# HB-power_v1_2.net
KiCad netlist of a schematic drawn in EAGLE
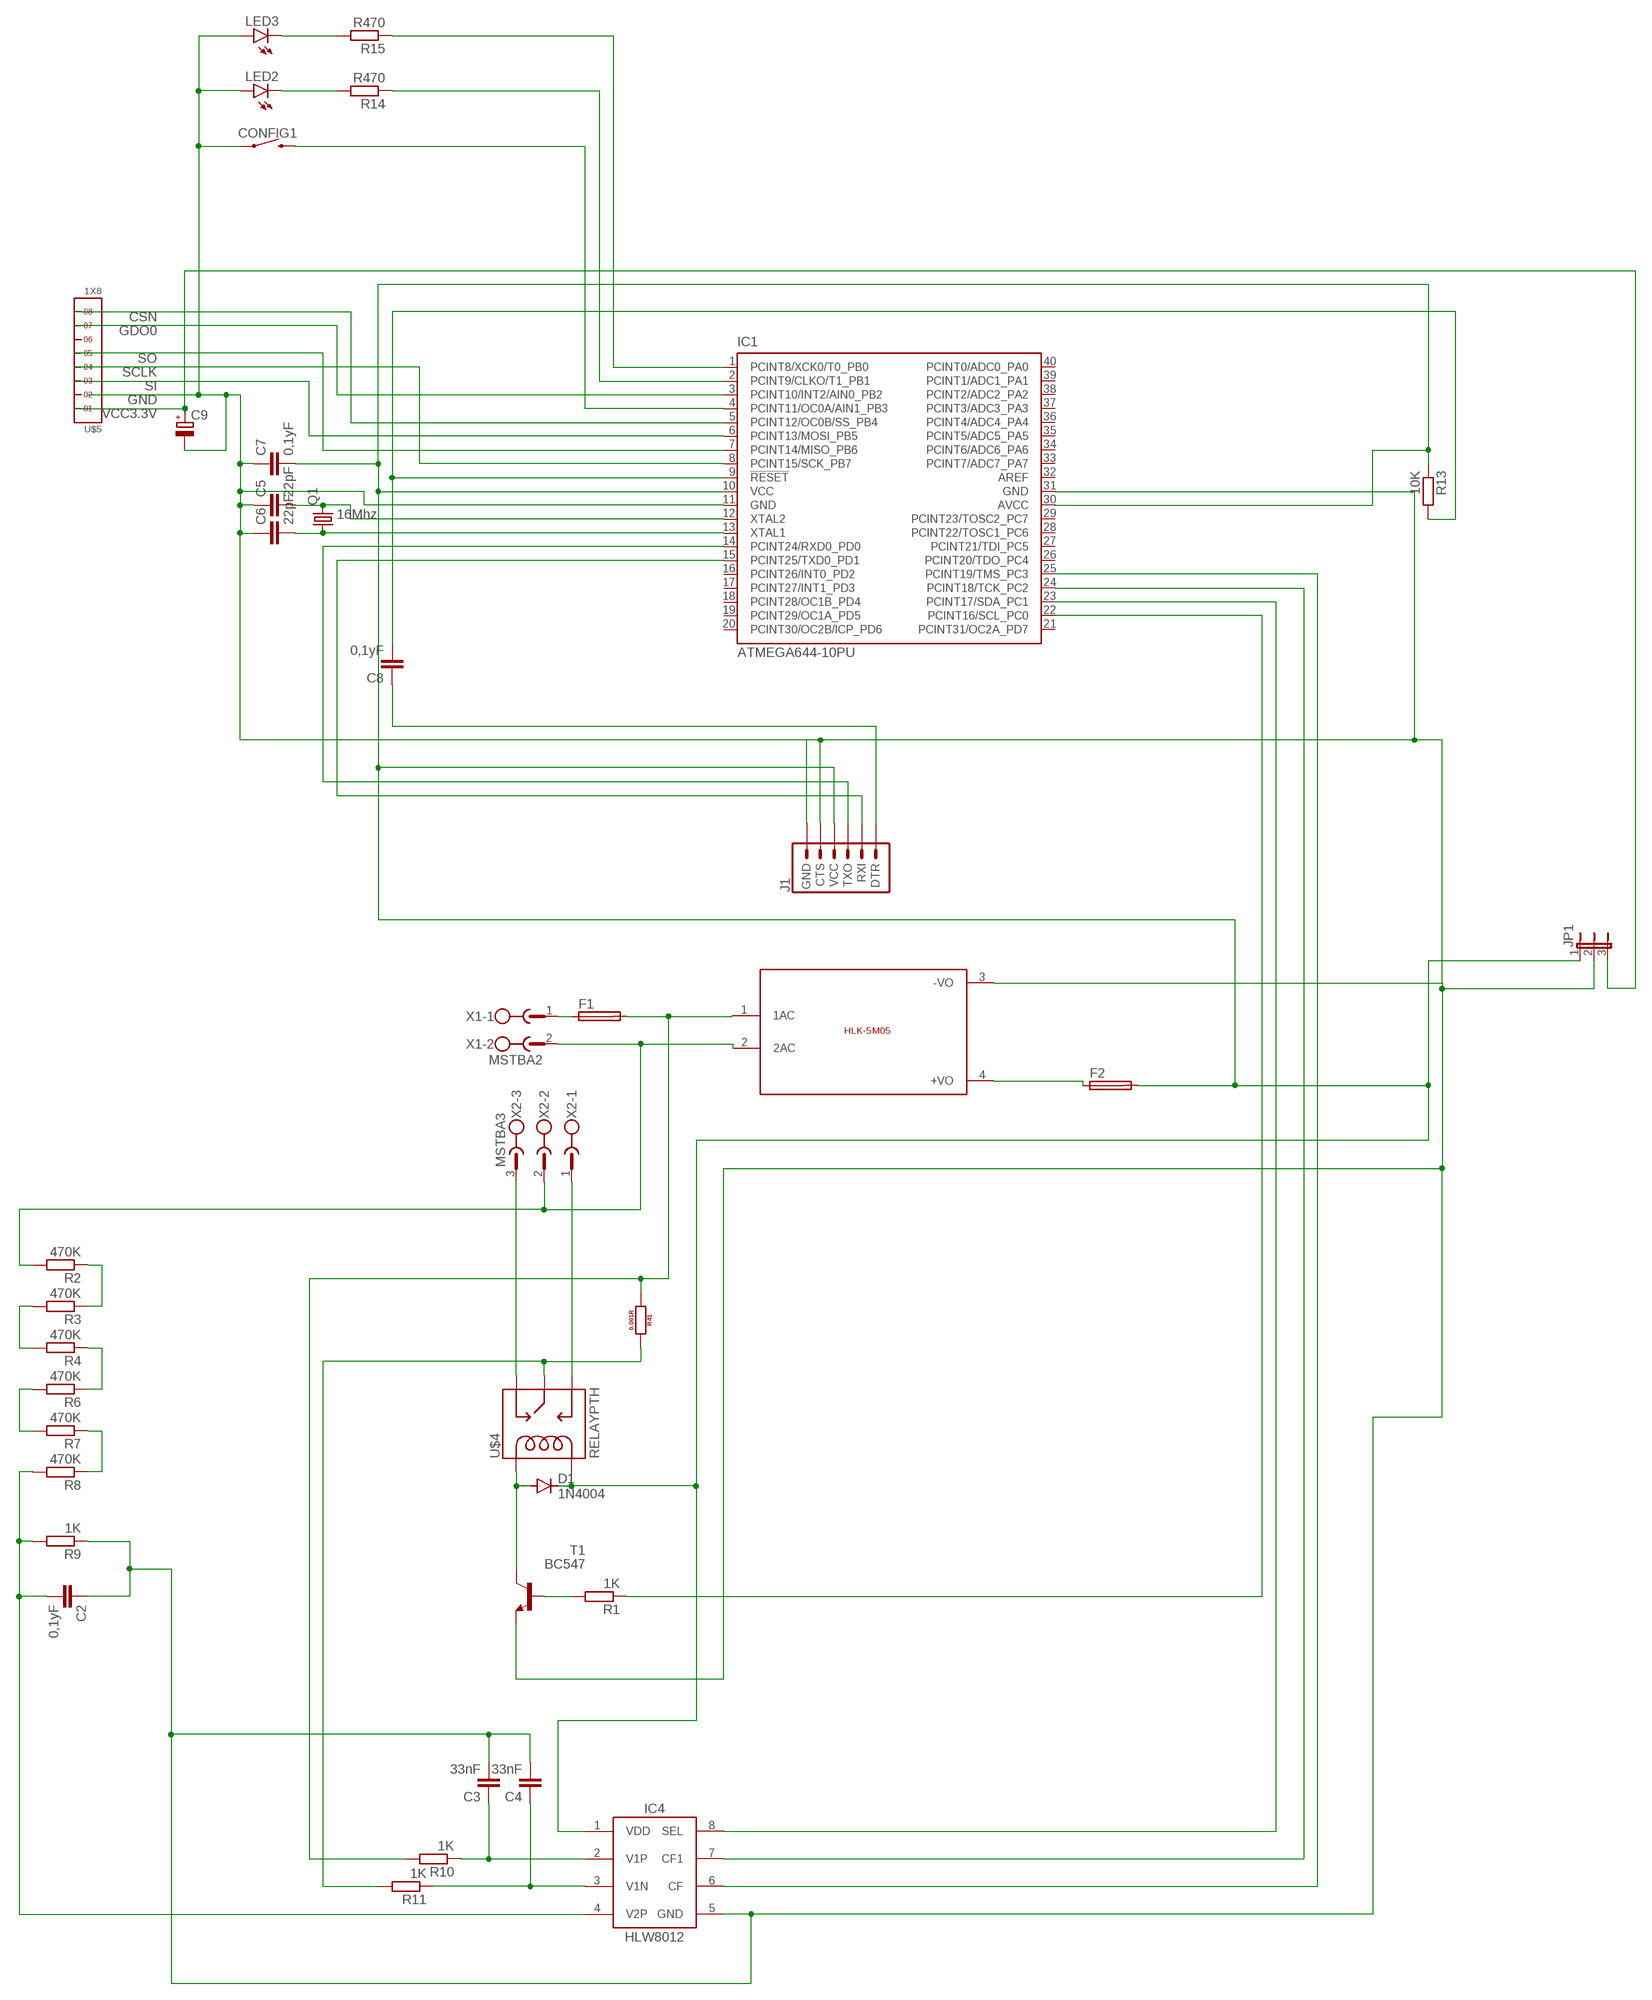
[diagram p0: schematic, sheet 1]

(export (version "E")
  (design (tool "Eeschema 10.0.6"))
  (components
    (comp (ref "C2")
      (value "0,1yF")
      (footprint "eagle-import:C050-024X044")
      (libsource (lib "eagle-import") (part "C-EU050-024X044"))
    )
    (comp (ref "C3")
      (value "33nF")
      (footprint "eagle-import:C050-024X044")
      (libsource (lib "eagle-import") (part "C-EU050-024X044"))
    )
    (comp (ref "C4")
      (value "33nF")
      (footprint "eagle-import:C050-024X044")
      (libsource (lib "eagle-import") (part "C-EU050-024X044"))
    )
    (comp (ref "C5")
      (value "22pF")
      (footprint "eagle-import:C025-024X044")
      (libsource (lib "eagle-import") (part "C-EU025-024X044"))
    )
    (comp (ref "C6")
      (value "22pF")
      (footprint "eagle-import:C025-024X044")
      (libsource (lib "eagle-import") (part "C-EU025-024X044"))
    )
    (comp (ref "C7")
      (value "0,1yF")
      (footprint "eagle-import:C025-024X044")
      (libsource (lib "eagle-import") (part "C-EU025-024X044"))
    )
    (comp (ref "C8")
      (value "0,1yF")
      (footprint "eagle-import:C025-024X044")
      (libsource (lib "eagle-import") (part "C-EU025-024X044"))
    )
    (comp (ref "C9")
      (value "CPOL-EUE2.5-5")
      (footprint "eagle-import:E2,5-5")
      (libsource (lib "eagle-import") (part "CPOL-EUE2.5-5"))
    )
    (comp (ref "CONFIG1")
      (value "MOMENTARY-SWITCH-SPST-PTH-6.0MM-KIT")
      (footprint "eagle-import:TACTILE_SWITCH_PTH_6.0MM_KIT")
      (libsource (lib "eagle-import") (part "MOMENTARY-SWITCH-SPST-PTH-6.0MM-KIT"))
    )
    (comp (ref "D1")
      (value "1N4004")
      (footprint "eagle-import:DO41-10")
      (libsource (lib "eagle-import") (part "1N4004"))
    )
    (comp (ref "F1")
      (value "SH22,5A")
      (footprint "eagle-import:SH22,5A")
      (fields (field (name "MPN") "0031.7701.11"))
      (libsource (lib "eagle-import") (part "SH22,5A"))
    )
    (comp (ref "F2")
      (value "SH22,5A")
      (footprint "eagle-import:SH22,5A")
      (fields (field (name "MPN") "0031.7701.11"))
      (libsource (lib "eagle-import") (part "SH22,5A"))
    )
    (comp (ref "IC1")
      (value "ATMEGA644-10PU")
      (footprint "eagle-import:DIL40")
      (fields (field (name "MPN") "ATMEGA644V-10PU"))
      (libsource (lib "eagle-import") (part "ATMEGA644-PU10"))
    )
    (comp (ref "IC4")
      (value "HLW8012")
      (footprint "eagle-import:SOP8")
      (libsource (lib "eagle-import") (part "HLW8012"))
    )
    (comp (ref "J1")
      (value "6_PIN_SERIAL_TARGETLONGPADS")
      (footprint "eagle-import:1X06_LONGPADS")
      (libsource (lib "eagle-import") (part "6_PIN_SERIAL_TARGETLONGPADS"))
    )
    (comp (ref "JP1")
      (value "JP2E")
      (footprint "eagle-import:JP2")
      (libsource (lib "eagle-import") (part "JP2E"))
    )
    (comp (ref "LED2")
      (value "LED3MM")
      (footprint "eagle-import:LED3MM")
      (libsource (lib "eagle-import") (part "LED3MM"))
    )
    (comp (ref "LED3")
      (value "LED3MM")
      (footprint "eagle-import:LED3MM")
      (libsource (lib "eagle-import") (part "LED3MM"))
    )
    (comp (ref "Q1")
      (value "16Mhz")
      (footprint "eagle-import:HC49U-V")
      (libsource (lib "eagle-import") (part "CRYSTALHC49U-V"))
    )
    (comp (ref "R1")
      (value "1K")
      (footprint "eagle-import:0309_10")
      (libsource (lib "eagle-import") (part "R-EU_0309/10"))
    )
    (comp (ref "R2")
      (value "470K")
      (footprint "eagle-import:0309_10")
      (libsource (lib "eagle-import") (part "R-EU_0309/10"))
    )
    (comp (ref "R3")
      (value "470K")
      (footprint "eagle-import:0309_10")
      (libsource (lib "eagle-import") (part "R-EU_0309/10"))
    )
    (comp (ref "R4")
      (value "470K")
      (footprint "eagle-import:0309_10")
      (libsource (lib "eagle-import") (part "R-EU_0309/10"))
    )
    (comp (ref "R6")
      (value "470K")
      (footprint "eagle-import:0309_10")
      (libsource (lib "eagle-import") (part "R-EU_0309/10"))
    )
    (comp (ref "R7")
      (value "470K")
      (footprint "eagle-import:0309_10")
      (libsource (lib "eagle-import") (part "R-EU_0309/10"))
    )
    (comp (ref "R8")
      (value "470K")
      (footprint "eagle-import:0309_10")
      (libsource (lib "eagle-import") (part "R-EU_0309/10"))
    )
    (comp (ref "R9")
      (value "1K")
      (footprint "eagle-import:0309_10")
      (libsource (lib "eagle-import") (part "R-EU_0309/10"))
    )
    (comp (ref "R10")
      (value "1K")
      (footprint "eagle-import:0309_10")
      (libsource (lib "eagle-import") (part "R-EU_0309/10"))
    )
    (comp (ref "R11")
      (value "1K")
      (footprint "eagle-import:0309_10")
      (libsource (lib "eagle-import") (part "R-EU_0309/10"))
    )
    (comp (ref "R13")
      (value "10K")
      (footprint "eagle-import:0309_10")
      (libsource (lib "eagle-import") (part "R-EU_0309/10"))
    )
    (comp (ref "R14")
      (value "R470")
      (footprint "eagle-import:0309_10")
      (libsource (lib "eagle-import") (part "R-EU_0309/10"))
    )
    (comp (ref "R15")
      (value "R470")
      (footprint "eagle-import:0309_10")
      (libsource (lib "eagle-import") (part "R-EU_0309/10"))
    )
    (comp (ref "R41")
      (value "0.001R")
      (footprint "eagle-import:2512")
      (libsource (lib "eagle-import") (part "RESISTOR2512"))
    )
    (comp (ref "T1")
      (value "BC547")
      (footprint "eagle-import:TO92")
      (libsource (lib "eagle-import") (part "BC547"))
    )
    (comp (ref "U$3")
      (value "5VDC/5W")
      (footprint "eagle-import:HLK-5M05")
      (libsource (lib "eagle-import") (part "HLK-5M05"))
    )
    (comp (ref "U$4")
      (value "RELAYPTH")
      (footprint "eagle-import:SRD-05VDC-SL-C")
      (libsource (lib "eagle-import") (part "RELAYPTH"))
    )
    (comp (ref "U$5")
      (value "1X8")
      (footprint "eagle-import:1X8")
      (libsource (lib "eagle-import") (part "1X8"))
    )
    (comp (ref "X1")
      (value "MSTBA2")
      (footprint "eagle-import:MSTBA2")
      (fields (field (name "MF") "FARNELL") (field (name "MPN") "1757242"))
      (libsource (lib "eagle-import") (part "MSTBA2"))
    )
    (comp (ref "X2")
      (value "MSTBA3")
      (footprint "eagle-import:MSTBA3")
      (fields (field (name "MF") "FARNELL") (field (name "MPN") "1757255"))
      (libsource (lib "eagle-import") (part "MSTBA3"))
    )
  )
  (nets
    (net (code "1") (name "/CSN") (class "Default")
      (node (ref "IC1") (pin "5") (pinfunction "PCINT12/OC0B/SS_PB4_5") (pintype "bidirectional"))
      (node (ref "U$5") (pin "8") (pinfunction "8_8") (pintype "bidirectional"))
    )
    (net (code "2") (name "/GDO0") (class "Default")
      (node (ref "IC1") (pin "3") (pinfunction "PCINT10/INT2/AIN0_PB2_3") (pintype "bidirectional"))
      (node (ref "U$5") (pin "7") (pinfunction "7_7") (pintype "bidirectional"))
    )
    (net (code "3") (name "/GND") (class "Default")
      (node (ref "C2") (pin "1") (pinfunction "1_1") (pintype "passive"))
      (node (ref "C3") (pin "2") (pinfunction "2_2") (pintype "passive"))
      (node (ref "C4") (pin "2") (pinfunction "2_2") (pintype "passive"))
      (node (ref "C5") (pin "1") (pinfunction "1_1") (pintype "passive"))
      (node (ref "C6") (pin "1") (pinfunction "1_1") (pintype "passive"))
      (node (ref "C7") (pin "1") (pinfunction "1_1") (pintype "passive"))
      (node (ref "C9") (pin "-") (pinfunction "-_-") (pintype "passive"))
      (node (ref "CONFIG1") (pin "1") (pinfunction "1_1") (pintype "passive"))
      (node (ref "IC1") (pin "11") (pinfunction "GND_11") (pintype "power_in"))
      (node (ref "IC1") (pin "31") (pinfunction "GND_31") (pintype "power_in"))
      (node (ref "IC4") (pin "5") (pinfunction "GND_5") (pintype "power_in"))
      (node (ref "J1") (pin "5") (pinfunction "CTS_5") (pintype "passive"))
      (node (ref "J1") (pin "6") (pinfunction "GND_6") (pintype "passive"))
      (node (ref "JP1") (pin "2") (pinfunction "2_2") (pintype "passive"))
      (node (ref "LED2") (pin "A") (pinfunction "A_A") (pintype "passive"))
      (node (ref "LED3") (pin "A") (pinfunction "A_A") (pintype "passive"))
      (node (ref "R9") (pin "1") (pinfunction "1_1") (pintype "passive"))
      (node (ref "T1") (pin "1") (pinfunction "E_1") (pintype "passive"))
      (node (ref "U$3") (pin "3") (pinfunction "-VO_3") (pintype "bidirectional"))
    )
    (net (code "4") (name "/SCLK") (class "Default")
      (node (ref "IC1") (pin "8") (pinfunction "PCINT15/SCK_PB7_8") (pintype "bidirectional"))
      (node (ref "U$5") (pin "4") (pinfunction "4_4") (pintype "bidirectional"))
    )
    (net (code "5") (name "/SI") (class "Default")
      (node (ref "IC1") (pin "6") (pinfunction "PCINT13/MOSI_PB5_6") (pintype "bidirectional"))
      (node (ref "U$5") (pin "3") (pinfunction "3_3") (pintype "bidirectional"))
    )
    (net (code "6") (name "/SO") (class "Default")
      (node (ref "IC1") (pin "7") (pinfunction "PCINT14/MISO_PB6_7") (pintype "bidirectional"))
      (node (ref "U$5") (pin "5") (pinfunction "5_5") (pintype "bidirectional"))
    )
    (net (code "7") (name "/VCC3.3V") (class "Default")
      (node (ref "C9") (pin "+") (pinfunction "+_+") (pintype "passive"))
      (node (ref "JP1") (pin "3") (pinfunction "3_3") (pintype "passive"))
      (node (ref "U$5") (pin "1") (pinfunction "1_1") (pintype "bidirectional"))
    )
    (net (code "8") (name "Net-(CONFIG1-2)") (class "Default")
      (node (ref "CONFIG1") (pin "3") (pinfunction "2_3") (pintype "passive"))
      (node (ref "IC1") (pin "4") (pinfunction "PCINT11/OC0A/AIN1_PB3_4") (pintype "bidirectional"))
    )
    (net (code "9") (name "Net-(F1-Pad1)") (class "Default")
      (node (ref "F1") (pin "1") (pinfunction "1_1") (pintype "passive"))
      (node (ref "X1") (pin "1") (pinfunction "1_1") (pintype "passive"))
    )
    (net (code "10") (name "Net-(IC1-AVCC)") (class "Default")
      (node (ref "C7") (pin "2") (pinfunction "2_2") (pintype "passive"))
      (node (ref "D1") (pin "C") (pinfunction "C_C") (pintype "passive"))
      (node (ref "F2") (pin "2") (pinfunction "2_2") (pintype "passive"))
      (node (ref "IC1") (pin "10") (pinfunction "VCC_10") (pintype "power_in"))
      (node (ref "IC1") (pin "30") (pinfunction "AVCC_30") (pintype "power_in"))
      (node (ref "IC4") (pin "1") (pinfunction "VDD_1") (pintype "power_in"))
      (node (ref "J1") (pin "4") (pinfunction "VCC_4") (pintype "passive"))
      (node (ref "JP1") (pin "1") (pinfunction "1_1") (pintype "passive"))
      (node (ref "R13") (pin "1") (pinfunction "1_1") (pintype "passive"))
      (node (ref "U$4") (pin "COIL0") (pinfunction "COIL0_COIL0") (pintype "bidirectional"))
    )
    (net (code "11") (name "Net-(IC1-PCINT8{slash}XCK0{slash}T0_PB0)") (class "Default")
      (node (ref "IC1") (pin "1") (pinfunction "PCINT8/XCK0/T0_PB0_1") (pintype "bidirectional"))
      (node (ref "R15") (pin "1") (pinfunction "1_1") (pintype "passive"))
    )
    (net (code "12") (name "Net-(IC1-PCINT9{slash}CLKO{slash}T1_PB1)") (class "Default")
      (node (ref "IC1") (pin "2") (pinfunction "PCINT9/CLKO/T1_PB1_2") (pintype "bidirectional"))
      (node (ref "R14") (pin "1") (pinfunction "1_1") (pintype "passive"))
    )
    (net (code "13") (name "Net-(IC1-PCINT16{slash}SCL_PC0)") (class "Default")
      (node (ref "IC1") (pin "22") (pinfunction "PCINT16/SCL_PC0_22") (pintype "bidirectional"))
      (node (ref "R1") (pin "1") (pinfunction "1_1") (pintype "passive"))
    )
    (net (code "14") (name "Net-(IC1-PCINT17{slash}SDA_PC1)") (class "Default")
      (node (ref "IC1") (pin "23") (pinfunction "PCINT17/SDA_PC1_23") (pintype "bidirectional"))
      (node (ref "IC4") (pin "8") (pinfunction "SEL_8") (pintype "input"))
    )
    (net (code "15") (name "Net-(IC1-PCINT18{slash}TCK_PC2)") (class "Default")
      (node (ref "IC1") (pin "24") (pinfunction "PCINT18/TCK_PC2_24") (pintype "bidirectional"))
      (node (ref "IC4") (pin "7") (pinfunction "CF1_7") (pintype "output"))
    )
    (net (code "16") (name "Net-(IC1-PCINT19{slash}TMS_PC3)") (class "Default")
      (node (ref "IC1") (pin "25") (pinfunction "PCINT19/TMS_PC3_25") (pintype "bidirectional"))
      (node (ref "IC4") (pin "6") (pinfunction "CF_6") (pintype "output"))
    )
    (net (code "17") (name "Net-(IC1-PCINT24{slash}RXD0_PD0)") (class "Default")
      (node (ref "IC1") (pin "14") (pinfunction "PCINT24/RXD0_PD0_14") (pintype "bidirectional"))
      (node (ref "J1") (pin "3") (pinfunction "TXO_3") (pintype "passive"))
    )
    (net (code "18") (name "Net-(IC1-PCINT25{slash}TXD0_PD1)") (class "Default")
      (node (ref "IC1") (pin "15") (pinfunction "PCINT25/TXD0_PD1_15") (pintype "bidirectional"))
      (node (ref "J1") (pin "2") (pinfunction "RXI_2") (pintype "passive"))
    )
    (net (code "19") (name "Net-(IC1-XTAL1)") (class "Default")
      (node (ref "C6") (pin "2") (pinfunction "2_2") (pintype "passive"))
      (node (ref "IC1") (pin "13") (pinfunction "XTAL1_13") (pintype "input"))
      (node (ref "Q1") (pin "1") (pinfunction "1_1") (pintype "passive"))
    )
    (net (code "20") (name "Net-(IC1-XTAL2)") (class "Default")
      (node (ref "C5") (pin "2") (pinfunction "2_2") (pintype "passive"))
      (node (ref "IC1") (pin "12") (pinfunction "XTAL2_12") (pintype "output"))
      (node (ref "Q1") (pin "2") (pinfunction "2_2") (pintype "passive"))
    )
    (net (code "21") (name "Net-(IC1-~{RESET})") (class "Default")
      (node (ref "C8") (pin "2") (pinfunction "2_2") (pintype "passive"))
      (node (ref "IC1") (pin "9") (pinfunction "~{RESET}_9") (pintype "input"))
      (node (ref "R13") (pin "2") (pinfunction "2_2") (pintype "passive"))
    )
    (net (code "22") (name "Net-(IC4-V1N)") (class "Default")
      (node (ref "C4") (pin "1") (pinfunction "1_1") (pintype "passive"))
      (node (ref "IC4") (pin "3") (pinfunction "V1N_3") (pintype "input"))
      (node (ref "R11") (pin "1") (pinfunction "1_1") (pintype "passive"))
    )
    (net (code "23") (name "Net-(IC4-V1P)") (class "Default")
      (node (ref "C3") (pin "1") (pinfunction "1_1") (pintype "passive"))
      (node (ref "IC4") (pin "2") (pinfunction "V1P_2") (pintype "input"))
      (node (ref "R10") (pin "1") (pinfunction "1_1") (pintype "passive"))
    )
    (net (code "24") (name "Net-(IC4-V2P)") (class "Default")
      (node (ref "C2") (pin "2") (pinfunction "2_2") (pintype "passive"))
      (node (ref "IC4") (pin "4") (pinfunction "V2P_4") (pintype "input"))
      (node (ref "R8") (pin "2") (pinfunction "2_2") (pintype "passive"))
      (node (ref "R9") (pin "2") (pinfunction "2_2") (pintype "passive"))
    )
    (net (code "25") (name "Net-(J1-DTR)") (class "Default")
      (node (ref "C8") (pin "1") (pinfunction "1_1") (pintype "passive"))
      (node (ref "J1") (pin "1") (pinfunction "DTR_1") (pintype "passive"))
    )
    (net (code "26") (name "Net-(LED2-C)") (class "Default")
      (node (ref "LED2") (pin "K") (pinfunction "C_K") (pintype "passive"))
      (node (ref "R14") (pin "2") (pinfunction "2_2") (pintype "passive"))
    )
    (net (code "27") (name "Net-(LED3-C)") (class "Default")
      (node (ref "LED3") (pin "K") (pinfunction "C_K") (pintype "passive"))
      (node (ref "R15") (pin "2") (pinfunction "2_2") (pintype "passive"))
    )
    (net (code "28") (name "Net-(R2-Pad1)") (class "Default")
      (node (ref "R2") (pin "1") (pinfunction "1_1") (pintype "passive"))
      (node (ref "R3") (pin "1") (pinfunction "1_1") (pintype "passive"))
    )
    (net (code "29") (name "Net-(R3-Pad2)") (class "Default")
      (node (ref "R3") (pin "2") (pinfunction "2_2") (pintype "passive"))
      (node (ref "R4") (pin "2") (pinfunction "2_2") (pintype "passive"))
    )
    (net (code "30") (name "Net-(R4-Pad1)") (class "Default")
      (node (ref "R4") (pin "1") (pinfunction "1_1") (pintype "passive"))
      (node (ref "R6") (pin "1") (pinfunction "1_1") (pintype "passive"))
    )
    (net (code "31") (name "Net-(R6-Pad2)") (class "Default")
      (node (ref "R6") (pin "2") (pinfunction "2_2") (pintype "passive"))
      (node (ref "R7") (pin "2") (pinfunction "2_2") (pintype "passive"))
    )
    (net (code "32") (name "Net-(R7-Pad1)") (class "Default")
      (node (ref "R7") (pin "1") (pinfunction "1_1") (pintype "passive"))
      (node (ref "R8") (pin "1") (pinfunction "1_1") (pintype "passive"))
    )
    (net (code "33") (name "Net-(R11-Pad2)") (class "Default")
      (node (ref "R11") (pin "2") (pinfunction "2_2") (pintype "passive"))
      (node (ref "R41") (pin "2") (pinfunction "2_2") (pintype "passive"))
      (node (ref "U$4") (pin "SWCOMMON") (pinfunction "SWCOMMON_SWCOMMON") (pintype "bidirectional"))
    )
    (net (code "34") (name "Net-(T1-B)") (class "Default")
      (node (ref "R1") (pin "2") (pinfunction "2_2") (pintype "passive"))
      (node (ref "T1") (pin "2") (pinfunction "B_2") (pintype "passive"))
    )
    (net (code "35") (name "Net-(T1-C)") (class "Default")
      (node (ref "D1") (pin "A") (pinfunction "A_A") (pintype "passive"))
      (node (ref "T1") (pin "3") (pinfunction "C_3") (pintype "passive"))
      (node (ref "U$4") (pin "COIL1") (pinfunction "COIL1_COIL1") (pintype "bidirectional"))
    )
    (net (code "36") (name "Net-(U$3-+VO)") (class "Default")
      (node (ref "F2") (pin "1") (pinfunction "1_1") (pintype "passive"))
      (node (ref "U$3") (pin "4") (pinfunction "+VO_4") (pintype "bidirectional"))
    )
    (net (code "37") (name "Net-(U$3-1AC)") (class "Default")
      (node (ref "F1") (pin "2") (pinfunction "2_2") (pintype "passive"))
      (node (ref "R10") (pin "2") (pinfunction "2_2") (pintype "passive"))
      (node (ref "R41") (pin "1") (pinfunction "1_1") (pintype "passive"))
      (node (ref "U$3") (pin "1") (pinfunction "1AC_1") (pintype "bidirectional"))
    )
    (net (code "38") (name "Net-(U$3-2AC)") (class "Default")
      (node (ref "R2") (pin "2") (pinfunction "2_2") (pintype "passive"))
      (node (ref "U$3") (pin "2") (pinfunction "2AC_2") (pintype "bidirectional"))
      (node (ref "X1") (pin "2") (pinfunction "1_2") (pintype "passive"))
      (node (ref "X2") (pin "2") (pinfunction "1_2") (pintype "passive"))
    )
    (net (code "39") (name "Net-(U$4-PadSWOPEN)") (class "Default")
      (node (ref "U$4") (pin "SWOPEN") (pinfunction "SWOPEN_SWOPEN") (pintype "bidirectional"))
      (node (ref "X2") (pin "1") (pinfunction "1_1") (pintype "passive"))
    )
    (net (code "40") (name "Net-(U$4-SWCLOSE)") (class "Default")
      (node (ref "U$4") (pin "SWCLOSED") (pinfunction "SWCLOSE_SWCLOSED") (pintype "bidirectional"))
      (node (ref "X2") (pin "3") (pinfunction "1_3") (pintype "passive"))
    )
    (net (code "41") (name "unconnected-(IC1-AREF-Pad32)") (class "Default")
      (node (ref "IC1") (pin "32") (pinfunction "AREF_32") (pintype "passive"))
    )
    (net (code "42") (name "unconnected-(IC1-PCINT0{slash}ADC0_PA0-Pad40)") (class "Default")
      (node (ref "IC1") (pin "40") (pinfunction "PCINT0/ADC0_PA0_40") (pintype "bidirectional"))
    )
    (net (code "43") (name "unconnected-(IC1-PCINT1{slash}ADC1_PA1-Pad39)") (class "Default")
      (node (ref "IC1") (pin "39") (pinfunction "PCINT1/ADC1_PA1_39") (pintype "bidirectional"))
    )
    (net (code "44") (name "unconnected-(IC1-PCINT2{slash}ADC2_PA2-Pad38)") (class "Default")
      (node (ref "IC1") (pin "38") (pinfunction "PCINT2/ADC2_PA2_38") (pintype "bidirectional"))
    )
    (net (code "45") (name "unconnected-(IC1-PCINT3{slash}ADC3_PA3-Pad37)") (class "Default")
      (node (ref "IC1") (pin "37") (pinfunction "PCINT3/ADC3_PA3_37") (pintype "bidirectional"))
    )
    (net (code "46") (name "unconnected-(IC1-PCINT4{slash}ADC4_PA4-Pad36)") (class "Default")
      (node (ref "IC1") (pin "36") (pinfunction "PCINT4/ADC4_PA4_36") (pintype "bidirectional"))
    )
    (net (code "47") (name "unconnected-(IC1-PCINT5{slash}ADC5_PA5-Pad35)") (class "Default")
      (node (ref "IC1") (pin "35") (pinfunction "PCINT5/ADC5_PA5_35") (pintype "bidirectional"))
    )
    (net (code "48") (name "unconnected-(IC1-PCINT6{slash}ADC6_PA6-Pad34)") (class "Default")
      (node (ref "IC1") (pin "34") (pinfunction "PCINT6/ADC6_PA6_34") (pintype "bidirectional"))
    )
    (net (code "49") (name "unconnected-(IC1-PCINT7{slash}ADC7_PA7-Pad33)") (class "Default")
      (node (ref "IC1") (pin "33") (pinfunction "PCINT7/ADC7_PA7_33") (pintype "bidirectional"))
    )
    (net (code "50") (name "unconnected-(IC1-PCINT20{slash}TDO_PC4-Pad26)") (class "Default")
      (node (ref "IC1") (pin "26") (pinfunction "PCINT20/TDO_PC4_26") (pintype "bidirectional"))
    )
    (net (code "51") (name "unconnected-(IC1-PCINT21{slash}TDI_PC5-Pad27)") (class "Default")
      (node (ref "IC1") (pin "27") (pinfunction "PCINT21/TDI_PC5_27") (pintype "bidirectional"))
    )
    (net (code "52") (name "unconnected-(IC1-PCINT22{slash}TOSC1_PC6-Pad28)") (class "Default")
      (node (ref "IC1") (pin "28") (pinfunction "PCINT22/TOSC1_PC6_28") (pintype "bidirectional"))
    )
    (net (code "53") (name "unconnected-(IC1-PCINT23{slash}TOSC2_PC7-Pad29)") (class "Default")
      (node (ref "IC1") (pin "29") (pinfunction "PCINT23/TOSC2_PC7_29") (pintype "bidirectional"))
    )
    (net (code "54") (name "unconnected-(IC1-PCINT26{slash}INT0_PD2-Pad16)") (class "Default")
      (node (ref "IC1") (pin "16") (pinfunction "PCINT26/INT0_PD2_16") (pintype "bidirectional"))
    )
    (net (code "55") (name "unconnected-(IC1-PCINT27{slash}INT1_PD3-Pad17)") (class "Default")
      (node (ref "IC1") (pin "17") (pinfunction "PCINT27/INT1_PD3_17") (pintype "bidirectional"))
    )
    (net (code "56") (name "unconnected-(IC1-PCINT28{slash}OC1B_PD4-Pad18)") (class "Default")
      (node (ref "IC1") (pin "18") (pinfunction "PCINT28/OC1B_PD4_18") (pintype "bidirectional"))
    )
    (net (code "57") (name "unconnected-(IC1-PCINT29{slash}OC1A_PD5-Pad19)") (class "Default")
      (node (ref "IC1") (pin "19") (pinfunction "PCINT29/OC1A_PD5_19") (pintype "bidirectional"))
    )
    (net (code "58") (name "unconnected-(IC1-PCINT30{slash}OC2B{slash}ICP_PD6-Pad20)") (class "Default")
      (node (ref "IC1") (pin "20") (pinfunction "PCINT30/OC2B/ICP_PD6_20") (pintype "bidirectional"))
    )
    (net (code "59") (name "unconnected-(IC1-PCINT31{slash}OC2A_PD7-Pad21)") (class "Default")
      (node (ref "IC1") (pin "21") (pinfunction "PCINT31/OC2A_PD7_21") (pintype "bidirectional"))
    )
    (net (code "60") (name "unconnected-(U$5-Pad2)") (class "Default")
      (node (ref "U$5") (pin "2") (pinfunction "2_2") (pintype "bidirectional"))
    )
    (net (code "61") (name "unconnected-(U$5-Pad6)") (class "Default")
      (node (ref "U$5") (pin "6") (pinfunction "6_6") (pintype "bidirectional"))
    )
  )
)
